# 2023-12-16_LVMi-IonPump-Controller.net
KiCad netlist of a schematic drawn in EAGLE
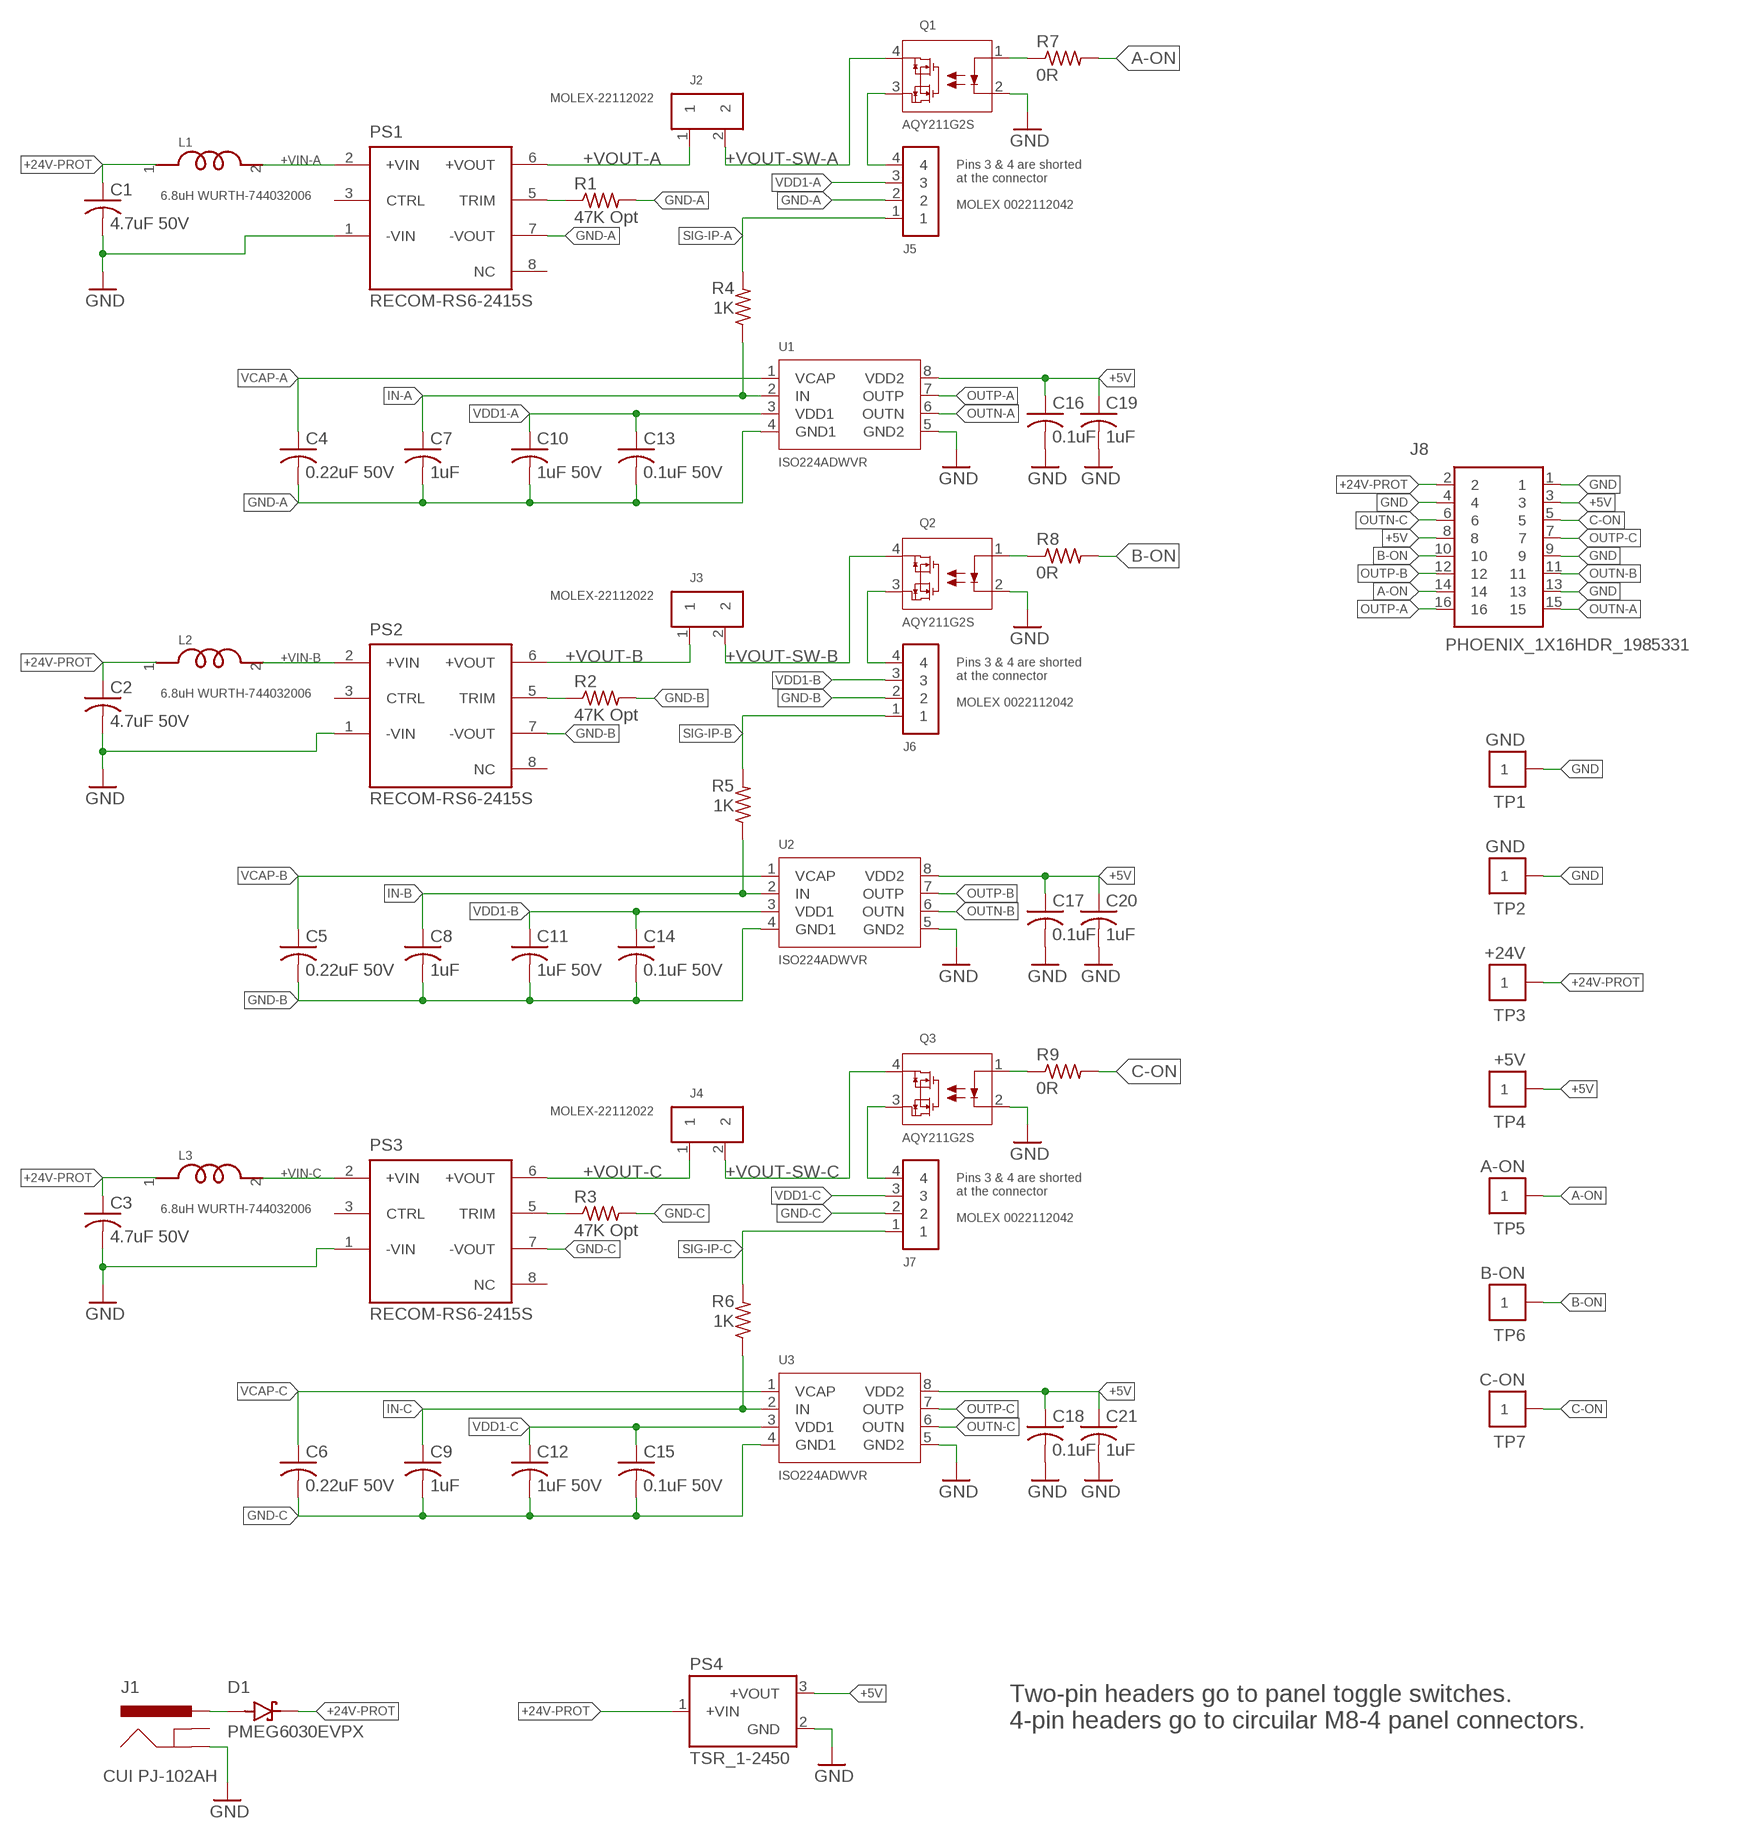
[diagram p0: schematic, sheet 1]

(export (version "E")
  (design (tool "Eeschema 10.0.6"))
  (components
    (comp (ref "C1")
      (value "4.7uF 50V")
      (footprint "eagle-import:C0805")
      (libsource (lib "eagle-import") (part "C-USC0805"))
    )
    (comp (ref "C2")
      (value "4.7uF 50V")
      (footprint "eagle-import:C0805")
      (libsource (lib "eagle-import") (part "C-USC0805"))
    )
    (comp (ref "C3")
      (value "4.7uF 50V")
      (footprint "eagle-import:C0805")
      (libsource (lib "eagle-import") (part "C-USC0805"))
    )
    (comp (ref "C4")
      (value "0.22uF 50V")
      (footprint "eagle-import:C0805")
      (libsource (lib "eagle-import") (part "C-USC0805"))
    )
    (comp (ref "C5")
      (value "0.22uF 50V")
      (footprint "eagle-import:C0805")
      (libsource (lib "eagle-import") (part "C-USC0805"))
    )
    (comp (ref "C6")
      (value "0.22uF 50V")
      (footprint "eagle-import:C0805")
      (libsource (lib "eagle-import") (part "C-USC0805"))
    )
    (comp (ref "C7")
      (value "1uF")
      (footprint "eagle-import:C0805")
      (libsource (lib "eagle-import") (part "C-USC0805"))
    )
    (comp (ref "C8")
      (value "1uF")
      (footprint "eagle-import:C0805")
      (libsource (lib "eagle-import") (part "C-USC0805"))
    )
    (comp (ref "C9")
      (value "1uF")
      (footprint "eagle-import:C0805")
      (libsource (lib "eagle-import") (part "C-USC0805"))
    )
    (comp (ref "C10")
      (value "1uF 50V")
      (footprint "eagle-import:C0805")
      (libsource (lib "eagle-import") (part "C-USC0805"))
    )
    (comp (ref "C11")
      (value "1uF 50V")
      (footprint "eagle-import:C0805")
      (libsource (lib "eagle-import") (part "C-USC0805"))
    )
    (comp (ref "C12")
      (value "1uF 50V")
      (footprint "eagle-import:C0805")
      (libsource (lib "eagle-import") (part "C-USC0805"))
    )
    (comp (ref "C13")
      (value "0.1uF 50V")
      (footprint "eagle-import:C0805")
      (libsource (lib "eagle-import") (part "C-USC0805"))
    )
    (comp (ref "C14")
      (value "0.1uF 50V")
      (footprint "eagle-import:C0805")
      (libsource (lib "eagle-import") (part "C-USC0805"))
    )
    (comp (ref "C15")
      (value "0.1uF 50V")
      (footprint "eagle-import:C0805")
      (libsource (lib "eagle-import") (part "C-USC0805"))
    )
    (comp (ref "C16")
      (value "0.1uF")
      (footprint "eagle-import:C0805")
      (libsource (lib "eagle-import") (part "C-USC0805"))
    )
    (comp (ref "C17")
      (value "0.1uF")
      (footprint "eagle-import:C0805")
      (libsource (lib "eagle-import") (part "C-USC0805"))
    )
    (comp (ref "C18")
      (value "0.1uF")
      (footprint "eagle-import:C0805")
      (libsource (lib "eagle-import") (part "C-USC0805"))
    )
    (comp (ref "C19")
      (value "1uF")
      (footprint "eagle-import:C0805")
      (libsource (lib "eagle-import") (part "C-USC0805"))
    )
    (comp (ref "C20")
      (value "1uF")
      (footprint "eagle-import:C0805")
      (libsource (lib "eagle-import") (part "C-USC0805"))
    )
    (comp (ref "C21")
      (value "1uF")
      (footprint "eagle-import:C0805")
      (libsource (lib "eagle-import") (part "C-USC0805"))
    )
    (comp (ref "D1")
      (value "PMEG6030EVPX")
      (footprint "eagle-import:DIO_PMEG6030EVPX")
      (fields (field (name "DIGI-KEY_PART_NUMBER") "1727-1349-1-ND") (field (name "MF") "Nexperia USA"))
      (libsource (lib "eagle-import") (part "SCHOTTKY-PMEG6030EVPX"))
    )
    (comp (ref "J1")
      (value "CUI PJ-102AH")
      (footprint "eagle-import:PJ-102AH")
      (libsource (lib "eagle-import") (part "POWER_JACKPJ-102AH"))
    )
    (comp (ref "J2")
      (value "MOLEX-22112022")
      (footprint "eagle-import:1X02-MOLEX-22112022")
      (libsource (lib "eagle-import") (part "PINHD-1X2-MOLEX-22112022"))
    )
    (comp (ref "J3")
      (value "MOLEX-22112022")
      (footprint "eagle-import:1X02-MOLEX-22112022")
      (libsource (lib "eagle-import") (part "PINHD-1X2-MOLEX-22112022"))
    )
    (comp (ref "J4")
      (value "MOLEX-22112022")
      (footprint "eagle-import:1X02-MOLEX-22112022")
      (libsource (lib "eagle-import") (part "PINHD-1X2-MOLEX-22112022"))
    )
    (comp (ref "J5")
      (value "MOLEX 0022112042")
      (footprint "eagle-import:1X04-MOLEX-22112042")
      (libsource (lib "eagle-import") (part "PINHD-1X4-MOLEX-22112042"))
    )
    (comp (ref "J6")
      (value "MOLEX 0022112042")
      (footprint "eagle-import:1X04-MOLEX-22112042")
      (libsource (lib "eagle-import") (part "PINHD-1X4-MOLEX-22112042"))
    )
    (comp (ref "J7")
      (value "MOLEX 0022112042")
      (footprint "eagle-import:1X04-MOLEX-22112042")
      (libsource (lib "eagle-import") (part "PINHD-1X4-MOLEX-22112042"))
    )
    (comp (ref "J8")
      (value "PHOENIX_1X16HDR_1985331")
      (footprint "eagle-import:1985331")
      (fields
        (field (name "MANUFACTURER_PART_NUMBER") "1985331")
        (field (name "MOUSER_PART_NUMBER") "651-1985331")
      )
      (libsource (lib "eagle-import") (part "PHOENIX_1X16HDR_1985331"))
    )
    (comp (ref "L1")
      (value "6.8uH WURTH-744032006")
      (footprint "eagle-import:WURTH-1210-INDUCTOR")
      (libsource (lib "eagle-import") (part "INDUCTOR-WURTH-744032006"))
    )
    (comp (ref "L2")
      (value "6.8uH WURTH-744032006")
      (footprint "eagle-import:WURTH-1210-INDUCTOR")
      (libsource (lib "eagle-import") (part "INDUCTOR-WURTH-744032006"))
    )
    (comp (ref "L3")
      (value "6.8uH WURTH-744032006")
      (footprint "eagle-import:WURTH-1210-INDUCTOR")
      (libsource (lib "eagle-import") (part "INDUCTOR-WURTH-744032006"))
    )
    (comp (ref "PS1")
      (value "RECOM-RS6-2415S")
      (footprint "eagle-import:CONV_RS6-2415S")
      (fields
        (field (name "DIGI-KEY_PART_NUMBER") "945-2987-ND")
        (field (name "MF") "Recom Power")
        (field (name "MP") "RS6-2415S")
      )
      (libsource (lib "eagle-import") (part "DC-DC-15V-RECOM-RS6-2415S"))
    )
    (comp (ref "PS2")
      (value "RECOM-RS6-2415S")
      (footprint "eagle-import:CONV_RS6-2415S")
      (fields
        (field (name "DIGI-KEY_PART_NUMBER") "945-2987-ND")
        (field (name "MF") "Recom Power")
        (field (name "MP") "RS6-2415S")
      )
      (libsource (lib "eagle-import") (part "DC-DC-15V-RECOM-RS6-2415S"))
    )
    (comp (ref "PS3")
      (value "RECOM-RS6-2415S")
      (footprint "eagle-import:CONV_RS6-2415S")
      (fields
        (field (name "DIGI-KEY_PART_NUMBER") "945-2987-ND")
        (field (name "MF") "Recom Power")
        (field (name "MP") "RS6-2415S")
      )
      (libsource (lib "eagle-import") (part "DC-DC-15V-RECOM-RS6-2415S"))
    )
    (comp (ref "PS4")
      (value "TSR_1-2450")
      (footprint "eagle-import:CONV_TSR_1-2450")
      (fields (field (name "MANUFACTURER") "Traco Power"))
      (libsource (lib "eagle-import") (part "TSR_1-2450"))
    )
    (comp (ref "Q1")
      (value "AQY211G2S")
      (footprint "eagle-import:SOP4_PAN")
      (fields
        (field (name "MANUFACTURER_PART_NUMBER") "AQY212GSX")
        (field (name "COPYRIGHT") "Copyright (C) 2023 Ultra Librarian. All rights reserved.")
      )
      (libsource (lib "eagle-import") (part "AQY212GSX"))
    )
    (comp (ref "Q2")
      (value "AQY211G2S")
      (footprint "eagle-import:SOP4_PAN")
      (fields
        (field (name "MANUFACTURER_PART_NUMBER") "AQY212GSX")
        (field (name "COPYRIGHT") "Copyright (C) 2023 Ultra Librarian. All rights reserved.")
      )
      (libsource (lib "eagle-import") (part "AQY212GSX"))
    )
    (comp (ref "Q3")
      (value "AQY211G2S")
      (footprint "eagle-import:SOP4_PAN")
      (fields
        (field (name "MANUFACTURER_PART_NUMBER") "AQY212GSX")
        (field (name "COPYRIGHT") "Copyright (C) 2023 Ultra Librarian. All rights reserved.")
      )
      (libsource (lib "eagle-import") (part "AQY212GSX"))
    )
    (comp (ref "R1")
      (value "47K Opt")
      (footprint "eagle-import:R0805")
      (libsource (lib "eagle-import") (part "R-US_R0805"))
    )
    (comp (ref "R2")
      (value "47K Opt")
      (footprint "eagle-import:R0805")
      (libsource (lib "eagle-import") (part "R-US_R0805"))
    )
    (comp (ref "R3")
      (value "47K Opt")
      (footprint "eagle-import:R0805")
      (libsource (lib "eagle-import") (part "R-US_R0805"))
    )
    (comp (ref "R4")
      (value "1K")
      (footprint "eagle-import:R0805")
      (libsource (lib "eagle-import") (part "R-US_R0805"))
    )
    (comp (ref "R5")
      (value "1K")
      (footprint "eagle-import:R0805")
      (libsource (lib "eagle-import") (part "R-US_R0805"))
    )
    (comp (ref "R6")
      (value "1K")
      (footprint "eagle-import:R0805")
      (libsource (lib "eagle-import") (part "R-US_R0805"))
    )
    (comp (ref "R7")
      (value "0R")
      (footprint "eagle-import:R0805")
      (libsource (lib "eagle-import") (part "R-US_R0805"))
    )
    (comp (ref "R8")
      (value "0R")
      (footprint "eagle-import:R0805")
      (libsource (lib "eagle-import") (part "R-US_R0805"))
    )
    (comp (ref "R9")
      (value "0R")
      (footprint "eagle-import:R0805")
      (libsource (lib "eagle-import") (part "R-US_R0805"))
    )
    (comp (ref "TP1")
      (value "GND")
      (footprint "eagle-import:TP5000-TESTPOINT-BLK")
      (libsource (lib "eagle-import") (part "TP5000-TESTPOINT-BLK"))
    )
    (comp (ref "TP2")
      (value "GND")
      (footprint "eagle-import:TP5000-TESTPOINT-BLK")
      (libsource (lib "eagle-import") (part "TP5000-TESTPOINT-BLK"))
    )
    (comp (ref "TP3")
      (value "+24V")
      (footprint "eagle-import:TP5000-TESTPOINT-BLK")
      (libsource (lib "eagle-import") (part "TP5000-TESTPOINT-BLK"))
    )
    (comp (ref "TP4")
      (value "+5V")
      (footprint "eagle-import:TP5000-TESTPOINT-BLK")
      (libsource (lib "eagle-import") (part "TP5000-TESTPOINT-BLK"))
    )
    (comp (ref "TP5")
      (value "A-ON")
      (footprint "eagle-import:TP5000-TESTPOINT-BLK")
      (libsource (lib "eagle-import") (part "TP5000-TESTPOINT-BLK"))
    )
    (comp (ref "TP6")
      (value "B-ON")
      (footprint "eagle-import:TP5000-TESTPOINT-BLK")
      (libsource (lib "eagle-import") (part "TP5000-TESTPOINT-BLK"))
    )
    (comp (ref "TP7")
      (value "C-ON")
      (footprint "eagle-import:TP5000-TESTPOINT-BLK")
      (libsource (lib "eagle-import") (part "TP5000-TESTPOINT-BLK"))
    )
    (comp (ref "U1")
      (value "ISO224ADWVR")
      (footprint "eagle-import:DWV8_TEX")
      (fields (field (name "COPYRIGHT") "Copyright (C) 2018 Accelerated Designs. All rights reserved"))
      (libsource (lib "eagle-import") (part "ISO224ADWVR"))
    )
    (comp (ref "U2")
      (value "ISO224ADWVR")
      (footprint "eagle-import:DWV8_TEX")
      (fields (field (name "COPYRIGHT") "Copyright (C) 2018 Accelerated Designs. All rights reserved"))
      (libsource (lib "eagle-import") (part "ISO224ADWVR"))
    )
    (comp (ref "U3")
      (value "ISO224ADWVR")
      (footprint "eagle-import:DWV8_TEX")
      (fields (field (name "COPYRIGHT") "Copyright (C) 2018 Accelerated Designs. All rights reserved"))
      (libsource (lib "eagle-import") (part "ISO224ADWVR"))
    )
  )
  (nets
    (net (code "1") (name "+5V") (class "Default")
      (node (ref "C16") (pin "1") (pinfunction "1_1") (pintype "passive"))
      (node (ref "C17") (pin "1") (pinfunction "1_1") (pintype "passive"))
      (node (ref "C18") (pin "1") (pinfunction "1_1") (pintype "passive"))
      (node (ref "C19") (pin "1") (pinfunction "1_1") (pintype "passive"))
      (node (ref "C20") (pin "1") (pinfunction "1_1") (pintype "passive"))
      (node (ref "C21") (pin "1") (pinfunction "1_1") (pintype "passive"))
      (node (ref "J8") (pin "3") (pinfunction "3_3") (pintype "bidirectional"))
      (node (ref "J8") (pin "8") (pinfunction "8_8") (pintype "bidirectional"))
      (node (ref "PS4") (pin "3") (pinfunction "+VOUT_3") (pintype "output"))
      (node (ref "TP4") (pin "P$1") (pinfunction "1_P$1") (pintype "bidirectional"))
      (node (ref "U1") (pin "8") (pinfunction "VDD2_8") (pintype "power_in"))
      (node (ref "U2") (pin "8") (pinfunction "VDD2_8") (pintype "power_in"))
      (node (ref "U3") (pin "8") (pinfunction "VDD2_8") (pintype "power_in"))
    )
    (net (code "2") (name "+24V-PROT") (class "Default")
      (node (ref "C1") (pin "1") (pinfunction "1_1") (pintype "passive"))
      (node (ref "C2") (pin "1") (pinfunction "1_1") (pintype "passive"))
      (node (ref "C3") (pin "1") (pinfunction "1_1") (pintype "passive"))
      (node (ref "D1") (pin "1") (pinfunction "K_1") (pintype "passive"))
      (node (ref "J8") (pin "2") (pinfunction "2_2") (pintype "bidirectional"))
      (node (ref "L1") (pin "1") (pinfunction "1_1") (pintype "bidirectional"))
      (node (ref "L2") (pin "1") (pinfunction "1_1") (pintype "bidirectional"))
      (node (ref "L3") (pin "1") (pinfunction "1_1") (pintype "bidirectional"))
      (node (ref "PS4") (pin "1") (pinfunction "+VIN_1") (pintype "input"))
      (node (ref "TP3") (pin "P$1") (pinfunction "1_P$1") (pintype "bidirectional"))
    )
    (net (code "3") (name "/+VIN-A") (class "Default")
      (node (ref "L1") (pin "2") (pinfunction "2_2") (pintype "bidirectional"))
      (node (ref "PS1") (pin "2") (pinfunction "+VIN_2") (pintype "input"))
    )
    (net (code "4") (name "/+VIN-B") (class "Default")
      (node (ref "L2") (pin "2") (pinfunction "2_2") (pintype "bidirectional"))
      (node (ref "PS2") (pin "2") (pinfunction "+VIN_2") (pintype "input"))
    )
    (net (code "5") (name "/+VIN-C") (class "Default")
      (node (ref "L3") (pin "2") (pinfunction "2_2") (pintype "bidirectional"))
      (node (ref "PS3") (pin "2") (pinfunction "+VIN_2") (pintype "input"))
    )
    (net (code "6") (name "/+VOUT-A") (class "Default")
      (node (ref "J2") (pin "1") (pinfunction "1_1") (pintype "bidirectional"))
      (node (ref "PS1") (pin "6") (pinfunction "+VOUT_6") (pintype "output"))
    )
    (net (code "7") (name "/+VOUT-B") (class "Default")
      (node (ref "J3") (pin "1") (pinfunction "1_1") (pintype "bidirectional"))
      (node (ref "PS2") (pin "6") (pinfunction "+VOUT_6") (pintype "output"))
    )
    (net (code "8") (name "/+VOUT-C") (class "Default")
      (node (ref "J4") (pin "1") (pinfunction "1_1") (pintype "bidirectional"))
      (node (ref "PS3") (pin "6") (pinfunction "+VOUT_6") (pintype "output"))
    )
    (net (code "9") (name "/+VOUT-SW-A") (class "Default")
      (node (ref "J2") (pin "2") (pinfunction "2_2") (pintype "bidirectional"))
      (node (ref "Q1") (pin "4") (pinfunction "4_4") (pintype "passive"))
    )
    (net (code "10") (name "/+VOUT-SW-B") (class "Default")
      (node (ref "J3") (pin "2") (pinfunction "2_2") (pintype "bidirectional"))
      (node (ref "Q2") (pin "4") (pinfunction "4_4") (pintype "passive"))
    )
    (net (code "11") (name "/+VOUT-SW-C") (class "Default")
      (node (ref "J4") (pin "2") (pinfunction "2_2") (pintype "bidirectional"))
      (node (ref "Q3") (pin "4") (pinfunction "4_4") (pintype "passive"))
    )
    (net (code "12") (name "A-ON") (class "Default")
      (node (ref "J8") (pin "14") (pinfunction "14_14") (pintype "bidirectional"))
      (node (ref "R7") (pin "2") (pinfunction "2_2") (pintype "passive"))
      (node (ref "TP5") (pin "P$1") (pinfunction "1_P$1") (pintype "bidirectional"))
    )
    (net (code "13") (name "B-ON") (class "Default")
      (node (ref "J8") (pin "10") (pinfunction "10_10") (pintype "bidirectional"))
      (node (ref "R8") (pin "2") (pinfunction "2_2") (pintype "passive"))
      (node (ref "TP6") (pin "P$1") (pinfunction "1_P$1") (pintype "bidirectional"))
    )
    (net (code "14") (name "C-ON") (class "Default")
      (node (ref "J8") (pin "5") (pinfunction "5_5") (pintype "bidirectional"))
      (node (ref "R9") (pin "2") (pinfunction "2_2") (pintype "passive"))
      (node (ref "TP7") (pin "P$1") (pinfunction "1_P$1") (pintype "bidirectional"))
    )
    (net (code "15") (name "GND") (class "Default")
      (node (ref "C1") (pin "2") (pinfunction "2_2") (pintype "passive"))
      (node (ref "C16") (pin "2") (pinfunction "2_2") (pintype "passive"))
      (node (ref "C17") (pin "2") (pinfunction "2_2") (pintype "passive"))
      (node (ref "C18") (pin "2") (pinfunction "2_2") (pintype "passive"))
      (node (ref "C19") (pin "2") (pinfunction "2_2") (pintype "passive"))
      (node (ref "C2") (pin "2") (pinfunction "2_2") (pintype "passive"))
      (node (ref "C20") (pin "2") (pinfunction "2_2") (pintype "passive"))
      (node (ref "C21") (pin "2") (pinfunction "2_2") (pintype "passive"))
      (node (ref "C3") (pin "2") (pinfunction "2_2") (pintype "passive"))
      (node (ref "J1") (pin "GND") (pinfunction "GND_GND") (pintype "bidirectional"))
      (node (ref "J8") (pin "1") (pinfunction "1_1") (pintype "bidirectional"))
      (node (ref "J8") (pin "13") (pinfunction "13_13") (pintype "bidirectional"))
      (node (ref "J8") (pin "4") (pinfunction "4_4") (pintype "bidirectional"))
      (node (ref "J8") (pin "9") (pinfunction "9_9") (pintype "bidirectional"))
      (node (ref "PS1") (pin "1") (pinfunction "-VIN_1") (pintype "input"))
      (node (ref "PS2") (pin "1") (pinfunction "-VIN_1") (pintype "input"))
      (node (ref "PS3") (pin "1") (pinfunction "-VIN_1") (pintype "input"))
      (node (ref "PS4") (pin "2") (pinfunction "GND_2") (pintype "power_in"))
      (node (ref "Q1") (pin "2") (pinfunction "2_2") (pintype "passive"))
      (node (ref "Q2") (pin "2") (pinfunction "2_2") (pintype "passive"))
      (node (ref "Q3") (pin "2") (pinfunction "2_2") (pintype "passive"))
      (node (ref "TP1") (pin "P$1") (pinfunction "1_P$1") (pintype "bidirectional"))
      (node (ref "TP2") (pin "P$1") (pinfunction "1_P$1") (pintype "bidirectional"))
      (node (ref "U1") (pin "5") (pinfunction "GND2_5") (pintype "power_in"))
      (node (ref "U2") (pin "5") (pinfunction "GND2_5") (pintype "power_in"))
      (node (ref "U3") (pin "5") (pinfunction "GND2_5") (pintype "power_in"))
    )
    (net (code "16") (name "GND-A") (class "Default")
      (node (ref "C10") (pin "2") (pinfunction "2_2") (pintype "passive"))
      (node (ref "C13") (pin "2") (pinfunction "2_2") (pintype "passive"))
      (node (ref "C4") (pin "2") (pinfunction "2_2") (pintype "passive"))
      (node (ref "C7") (pin "2") (pinfunction "2_2") (pintype "passive"))
      (node (ref "J5") (pin "2") (pinfunction "2_2") (pintype "bidirectional"))
      (node (ref "PS1") (pin "7") (pinfunction "-VOUT_7") (pintype "output"))
      (node (ref "R1") (pin "2") (pinfunction "2_2") (pintype "passive"))
      (node (ref "U1") (pin "4") (pinfunction "GND1_4") (pintype "power_in"))
    )
    (net (code "17") (name "GND-B") (class "Default")
      (node (ref "C11") (pin "2") (pinfunction "2_2") (pintype "passive"))
      (node (ref "C14") (pin "2") (pinfunction "2_2") (pintype "passive"))
      (node (ref "C5") (pin "2") (pinfunction "2_2") (pintype "passive"))
      (node (ref "C8") (pin "2") (pinfunction "2_2") (pintype "passive"))
      (node (ref "J6") (pin "2") (pinfunction "2_2") (pintype "bidirectional"))
      (node (ref "PS2") (pin "7") (pinfunction "-VOUT_7") (pintype "output"))
      (node (ref "R2") (pin "2") (pinfunction "2_2") (pintype "passive"))
      (node (ref "U2") (pin "4") (pinfunction "GND1_4") (pintype "power_in"))
    )
    (net (code "18") (name "GND-C") (class "Default")
      (node (ref "C12") (pin "2") (pinfunction "2_2") (pintype "passive"))
      (node (ref "C15") (pin "2") (pinfunction "2_2") (pintype "passive"))
      (node (ref "C6") (pin "2") (pinfunction "2_2") (pintype "passive"))
      (node (ref "C9") (pin "2") (pinfunction "2_2") (pintype "passive"))
      (node (ref "J7") (pin "2") (pinfunction "2_2") (pintype "bidirectional"))
      (node (ref "PS3") (pin "7") (pinfunction "-VOUT_7") (pintype "output"))
      (node (ref "R3") (pin "2") (pinfunction "2_2") (pintype "passive"))
      (node (ref "U3") (pin "4") (pinfunction "GND1_4") (pintype "power_in"))
    )
    (net (code "19") (name "IN-A") (class "Default")
      (node (ref "C7") (pin "1") (pinfunction "1_1") (pintype "passive"))
      (node (ref "R4") (pin "1") (pinfunction "1_1") (pintype "passive"))
      (node (ref "U1") (pin "2") (pinfunction "IN_2") (pintype "input"))
    )
    (net (code "20") (name "IN-B") (class "Default")
      (node (ref "C8") (pin "1") (pinfunction "1_1") (pintype "passive"))
      (node (ref "R5") (pin "1") (pinfunction "1_1") (pintype "passive"))
      (node (ref "U2") (pin "2") (pinfunction "IN_2") (pintype "input"))
    )
    (net (code "21") (name "IN-C") (class "Default")
      (node (ref "C9") (pin "1") (pinfunction "1_1") (pintype "passive"))
      (node (ref "R6") (pin "1") (pinfunction "1_1") (pintype "passive"))
      (node (ref "U3") (pin "2") (pinfunction "IN_2") (pintype "input"))
    )
    (net (code "22") (name "Net-(D1-A)") (class "Default")
      (node (ref "D1") (pin "2") (pinfunction "A_2") (pintype "passive"))
      (node (ref "J1") (pin "PWR") (pinfunction "PWR_PWR") (pintype "bidirectional"))
    )
    (net (code "23") (name "Net-(J5-Pad4)") (class "Default")
      (node (ref "J5") (pin "4") (pinfunction "4_4") (pintype "bidirectional"))
      (node (ref "Q1") (pin "3") (pinfunction "3_3") (pintype "passive"))
    )
    (net (code "24") (name "Net-(J6-Pad4)") (class "Default")
      (node (ref "J6") (pin "4") (pinfunction "4_4") (pintype "bidirectional"))
      (node (ref "Q2") (pin "3") (pinfunction "3_3") (pintype "passive"))
    )
    (net (code "25") (name "Net-(J7-Pad4)") (class "Default")
      (node (ref "J7") (pin "4") (pinfunction "4_4") (pintype "bidirectional"))
      (node (ref "Q3") (pin "3") (pinfunction "3_3") (pintype "passive"))
    )
    (net (code "26") (name "Net-(PS1-TRIM)") (class "Default")
      (node (ref "PS1") (pin "5") (pinfunction "TRIM_5") (pintype "passive"))
      (node (ref "R1") (pin "1") (pinfunction "1_1") (pintype "passive"))
    )
    (net (code "27") (name "Net-(PS2-TRIM)") (class "Default")
      (node (ref "PS2") (pin "5") (pinfunction "TRIM_5") (pintype "passive"))
      (node (ref "R2") (pin "1") (pinfunction "1_1") (pintype "passive"))
    )
    (net (code "28") (name "Net-(PS3-TRIM)") (class "Default")
      (node (ref "PS3") (pin "5") (pinfunction "TRIM_5") (pintype "passive"))
      (node (ref "R3") (pin "1") (pinfunction "1_1") (pintype "passive"))
    )
    (net (code "29") (name "Net-(Q1-Pad1)") (class "Default")
      (node (ref "Q1") (pin "1") (pinfunction "1_1") (pintype "passive"))
      (node (ref "R7") (pin "1") (pinfunction "1_1") (pintype "passive"))
    )
    (net (code "30") (name "Net-(Q2-Pad1)") (class "Default")
      (node (ref "Q2") (pin "1") (pinfunction "1_1") (pintype "passive"))
      (node (ref "R8") (pin "1") (pinfunction "1_1") (pintype "passive"))
    )
    (net (code "31") (name "Net-(Q3-Pad1)") (class "Default")
      (node (ref "Q3") (pin "1") (pinfunction "1_1") (pintype "passive"))
      (node (ref "R9") (pin "1") (pinfunction "1_1") (pintype "passive"))
    )
    (net (code "32") (name "OUTN-A") (class "Default")
      (node (ref "J8") (pin "15") (pinfunction "15_15") (pintype "bidirectional"))
      (node (ref "U1") (pin "6") (pinfunction "OUTN_6") (pintype "output"))
    )
    (net (code "33") (name "OUTN-B") (class "Default")
      (node (ref "J8") (pin "11") (pinfunction "11_11") (pintype "bidirectional"))
      (node (ref "U2") (pin "6") (pinfunction "OUTN_6") (pintype "output"))
    )
    (net (code "34") (name "OUTN-C") (class "Default")
      (node (ref "J8") (pin "6") (pinfunction "6_6") (pintype "bidirectional"))
      (node (ref "U3") (pin "6") (pinfunction "OUTN_6") (pintype "output"))
    )
    (net (code "35") (name "OUTP-A") (class "Default")
      (node (ref "J8") (pin "16") (pinfunction "16_16") (pintype "bidirectional"))
      (node (ref "U1") (pin "7") (pinfunction "OUTP_7") (pintype "output"))
    )
    (net (code "36") (name "OUTP-B") (class "Default")
      (node (ref "J8") (pin "12") (pinfunction "12_12") (pintype "bidirectional"))
      (node (ref "U2") (pin "7") (pinfunction "OUTP_7") (pintype "output"))
    )
    (net (code "37") (name "OUTP-C") (class "Default")
      (node (ref "J8") (pin "7") (pinfunction "7_7") (pintype "bidirectional"))
      (node (ref "U3") (pin "7") (pinfunction "OUTP_7") (pintype "output"))
    )
    (net (code "38") (name "SIG-IP-A") (class "Default")
      (node (ref "J5") (pin "1") (pinfunction "1_1") (pintype "bidirectional"))
      (node (ref "R4") (pin "2") (pinfunction "2_2") (pintype "passive"))
    )
    (net (code "39") (name "SIG-IP-B") (class "Default")
      (node (ref "J6") (pin "1") (pinfunction "1_1") (pintype "bidirectional"))
      (node (ref "R5") (pin "2") (pinfunction "2_2") (pintype "passive"))
    )
    (net (code "40") (name "SIG-IP-C") (class "Default")
      (node (ref "J7") (pin "1") (pinfunction "1_1") (pintype "bidirectional"))
      (node (ref "R6") (pin "2") (pinfunction "2_2") (pintype "passive"))
    )
    (net (code "41") (name "VCAP-A") (class "Default")
      (node (ref "C4") (pin "1") (pinfunction "1_1") (pintype "passive"))
      (node (ref "U1") (pin "1") (pinfunction "VCAP_1") (pintype "power_in"))
    )
    (net (code "42") (name "VCAP-B") (class "Default")
      (node (ref "C5") (pin "1") (pinfunction "1_1") (pintype "passive"))
      (node (ref "U2") (pin "1") (pinfunction "VCAP_1") (pintype "power_in"))
    )
    (net (code "43") (name "VCAP-C") (class "Default")
      (node (ref "C6") (pin "1") (pinfunction "1_1") (pintype "passive"))
      (node (ref "U3") (pin "1") (pinfunction "VCAP_1") (pintype "power_in"))
    )
    (net (code "44") (name "VDD1-A") (class "Default")
      (node (ref "C10") (pin "1") (pinfunction "1_1") (pintype "passive"))
      (node (ref "C13") (pin "1") (pinfunction "1_1") (pintype "passive"))
      (node (ref "J5") (pin "3") (pinfunction "3_3") (pintype "bidirectional"))
      (node (ref "U1") (pin "3") (pinfunction "VDD1_3") (pintype "power_in"))
    )
    (net (code "45") (name "VDD1-B") (class "Default")
      (node (ref "C11") (pin "1") (pinfunction "1_1") (pintype "passive"))
      (node (ref "C14") (pin "1") (pinfunction "1_1") (pintype "passive"))
      (node (ref "J6") (pin "3") (pinfunction "3_3") (pintype "bidirectional"))
      (node (ref "U2") (pin "3") (pinfunction "VDD1_3") (pintype "power_in"))
    )
    (net (code "46") (name "VDD1-C") (class "Default")
      (node (ref "C12") (pin "1") (pinfunction "1_1") (pintype "passive"))
      (node (ref "C15") (pin "1") (pinfunction "1_1") (pintype "passive"))
      (node (ref "J7") (pin "3") (pinfunction "3_3") (pintype "bidirectional"))
      (node (ref "U3") (pin "3") (pinfunction "VDD1_3") (pintype "power_in"))
    )
    (net (code "47") (name "unconnected-(J1-GNDBREAK-PadGNDBRK)") (class "Default")
      (node (ref "J1") (pin "GNDBRK") (pinfunction "GNDBREAK_GNDBRK") (pintype "bidirectional"))
    )
    (net (code "48") (name "unconnected-(PS1-CTRL-Pad3)") (class "Default")
      (node (ref "PS1") (pin "3") (pinfunction "CTRL_3") (pintype "input"))
    )
    (net (code "49") (name "unconnected-(PS1-NC-Pad8)") (class "Default")
      (node (ref "PS1") (pin "8") (pinfunction "NC_8") (pintype "no_connect"))
    )
    (net (code "50") (name "unconnected-(PS2-CTRL-Pad3)") (class "Default")
      (node (ref "PS2") (pin "3") (pinfunction "CTRL_3") (pintype "input"))
    )
    (net (code "51") (name "unconnected-(PS2-NC-Pad8)") (class "Default")
      (node (ref "PS2") (pin "8") (pinfunction "NC_8") (pintype "no_connect"))
    )
    (net (code "52") (name "unconnected-(PS3-CTRL-Pad3)") (class "Default")
      (node (ref "PS3") (pin "3") (pinfunction "CTRL_3") (pintype "input"))
    )
    (net (code "53") (name "unconnected-(PS3-NC-Pad8)") (class "Default")
      (node (ref "PS3") (pin "8") (pinfunction "NC_8") (pintype "no_connect"))
    )
  )
)
